# BazzFussTrueBypass.net
KiCad netlist of a schematic drawn in EAGLE
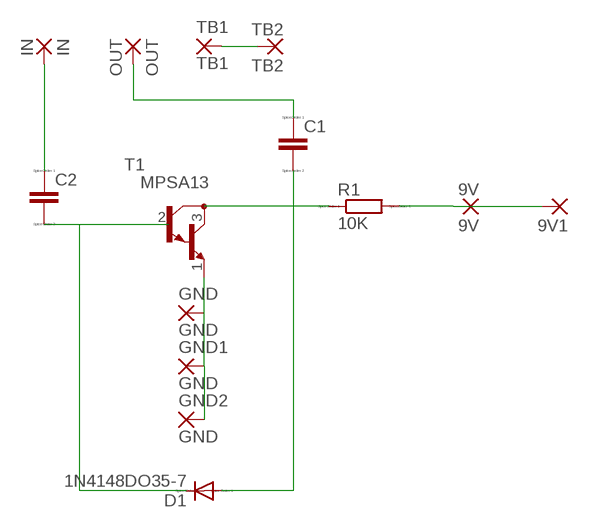
[diagram p0: schematic, sheet 1]

(export (version "E")
  (design (tool "Eeschema 10.0.6"))
  (components
    (comp (ref "9V")
      (value "9V")
      (footprint "eagle-import:1,6_0,8")
      (libsource (lib "eagle-import") (part "1,6/0,8"))
    )
    (comp (ref "9V1")
      (value "1,6/0,8")
      (footprint "eagle-import:1,6_0,8")
      (libsource (lib "eagle-import") (part "1,6/0,8"))
    )
    (comp (ref "C1")
      (value "C-EU025-025X050")
      (footprint "eagle-import:C025-025X050")
      (libsource (lib "eagle-import") (part "C-EU025-025X050"))
    )
    (comp (ref "C2")
      (value "C-EU025-025X050")
      (footprint "eagle-import:C025-025X050")
      (libsource (lib "eagle-import") (part "C-EU025-025X050"))
    )
    (comp (ref "D1")
      (value "1N4148DO35-7")
      (footprint "eagle-import:DO35-7")
      (libsource (lib "eagle-import") (part "1N4148DO35-7"))
    )
    (comp (ref "GND")
      (value "GND")
      (footprint "eagle-import:1,6_0,8")
      (libsource (lib "eagle-import") (part "1,6/0,8"))
    )
    (comp (ref "GND1")
      (value "GND")
      (footprint "eagle-import:1,6_0,8")
      (libsource (lib "eagle-import") (part "1,6/0,8"))
    )
    (comp (ref "GND2")
      (value "GND")
      (footprint "eagle-import:1,6_0,8")
      (libsource (lib "eagle-import") (part "1,6/0,8"))
    )
    (comp (ref "IN")
      (value "IN")
      (footprint "eagle-import:1,6_0,8")
      (libsource (lib "eagle-import") (part "1,6/0,8"))
    )
    (comp (ref "OUT")
      (value "OUT")
      (footprint "eagle-import:1,6_0,8")
      (libsource (lib "eagle-import") (part "1,6/0,8"))
    )
    (comp (ref "R1")
      (value "10K")
      (footprint "eagle-import:0207_10")
      (libsource (lib "eagle-import") (part "R0207/10"))
    )
    (comp (ref "T1")
      (value "MPSA13")
      (footprint "eagle-import:TO92")
      (libsource (lib "eagle-import") (part "BC517"))
    )
    (comp (ref "TB1")
      (value "TB1")
      (footprint "eagle-import:1,6_0,8")
      (libsource (lib "eagle-import") (part "1,6/0,8"))
    )
    (comp (ref "TB2")
      (value "TB2")
      (footprint "eagle-import:1,6_0,8")
      (libsource (lib "eagle-import") (part "1,6/0,8"))
    )
  )
  (nets
    (net (code "1") (name "Net-(9V-P)") (class "Default")
      (node (ref "9V") (pin "1") (pinfunction "P_1") (pintype "passive"))
      (node (ref "9V1") (pin "1") (pinfunction "P_1") (pintype "passive"))
      (node (ref "R1") (pin "2") (pinfunction "2_2") (pintype "passive"))
    )
    (net (code "2") (name "Net-(GND-P)") (class "Default")
      (node (ref "GND") (pin "1") (pinfunction "P_1") (pintype "passive"))
      (node (ref "GND1") (pin "1") (pinfunction "P_1") (pintype "passive"))
      (node (ref "GND2") (pin "1") (pinfunction "P_1") (pintype "passive"))
      (node (ref "T1") (pin "1") (pinfunction "E_1") (pintype "passive"))
    )
    (net (code "3") (name "Net-(IN-P)") (class "Default")
      (node (ref "C2") (pin "1") (pinfunction "1_1") (pintype "passive"))
      (node (ref "IN") (pin "1") (pinfunction "P_1") (pintype "passive"))
    )
    (net (code "4") (name "Net-(OUT-P)") (class "Default")
      (node (ref "C1") (pin "1") (pinfunction "1_1") (pintype "passive"))
      (node (ref "OUT") (pin "1") (pinfunction "P_1") (pintype "passive"))
    )
    (net (code "5") (name "Net-(T1-B)") (class "Default")
      (node (ref "C2") (pin "2") (pinfunction "2_2") (pintype "passive"))
      (node (ref "D1") (pin "C") (pinfunction "C_C") (pintype "passive"))
      (node (ref "T1") (pin "2") (pinfunction "B_2") (pintype "passive"))
    )
    (net (code "6") (name "Net-(T1-C)") (class "Default")
      (node (ref "C1") (pin "2") (pinfunction "2_2") (pintype "passive"))
      (node (ref "D1") (pin "A") (pinfunction "A_A") (pintype "passive"))
      (node (ref "R1") (pin "1") (pinfunction "1_1") (pintype "passive"))
      (node (ref "T1") (pin "3") (pinfunction "C_3") (pintype "passive"))
    )
    (net (code "7") (name "Net-(TB1-P)") (class "Default")
      (node (ref "TB1") (pin "1") (pinfunction "P_1") (pintype "passive"))
      (node (ref "TB2") (pin "1") (pinfunction "P_1") (pintype "passive"))
    )
  )
)
